# PAGE2_-_SFP_CONNECTORS_POWER.net
KiCad netlist of a schematic drawn in Altium Designer
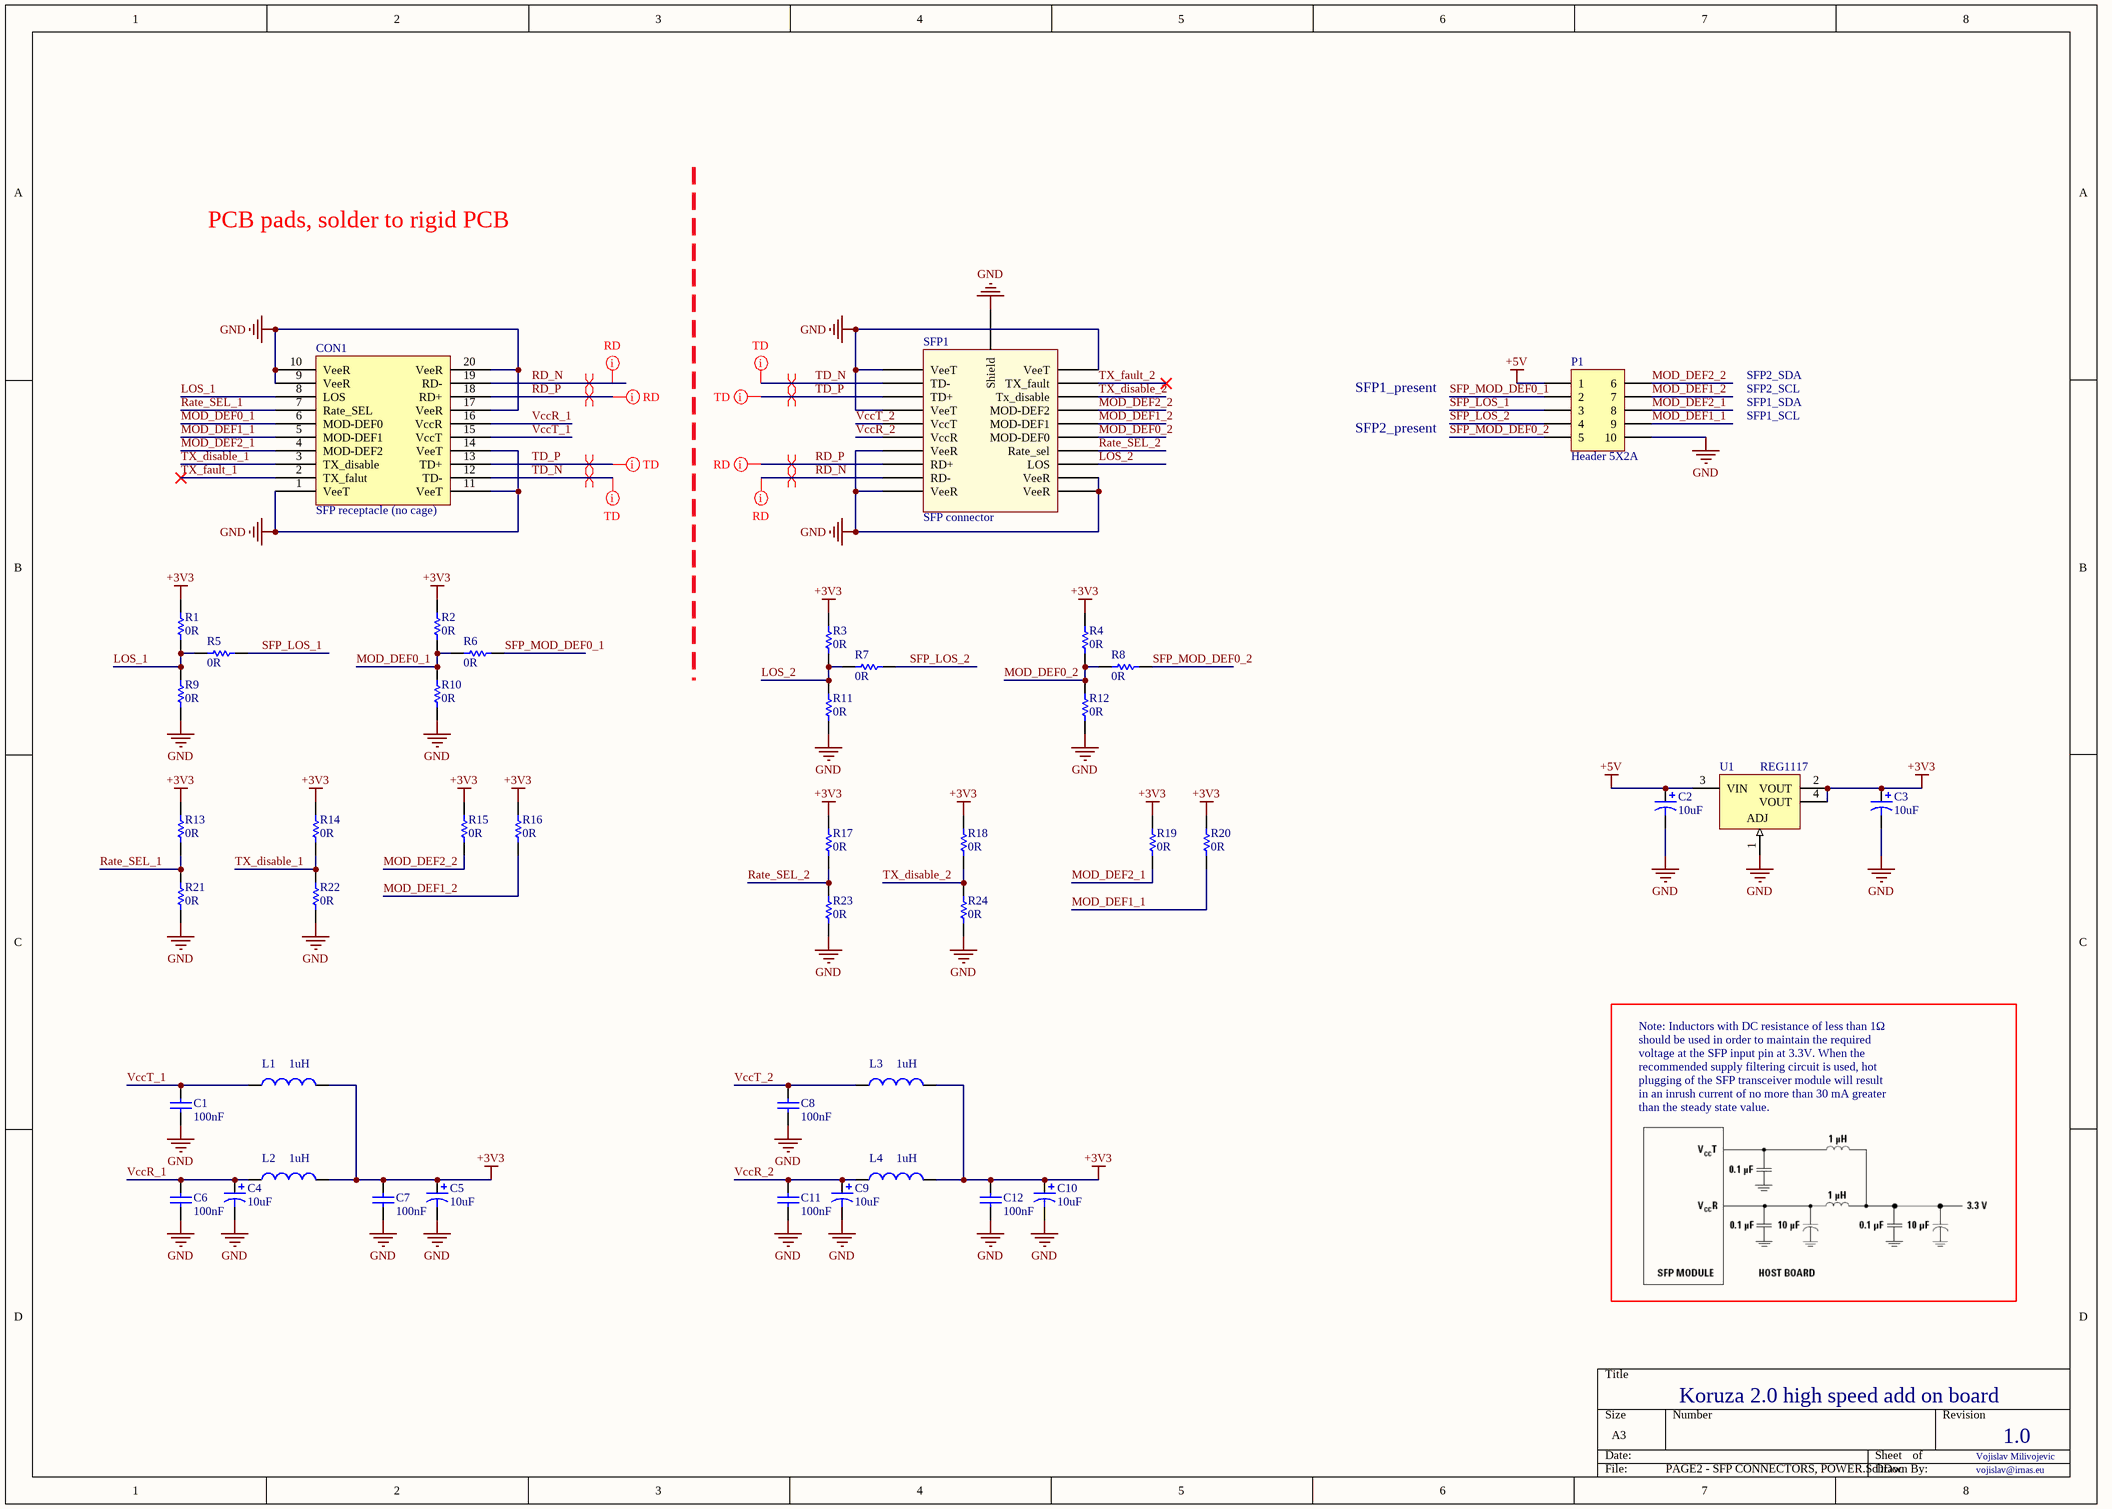
[diagram p0: PAGE2 - SFP CONNECTORS, POWER.SchDoc]

(export (version "E")
  (design (tool "Eeschema 10.0.6"))
  (components
    (comp (ref "C1")
      (value "100nF")
      (footprint "CAP0603")
      (description "Capacitor")
      (fields (field (name "PUBLISHER") "Altium Limited"))
      (libsource (lib "Miscellaneous Devices") (part "Cap"))
    )
    (comp (ref "C2")
      (value "10uF")
      (footprint "CAP0805")
      (description "Polarized Capacitor (Radial)")
      (fields (field (name "PUBLISHER") "Altium Limited"))
      (libsource (lib "PcvLib") (part "CAP0805"))
    )
    (comp (ref "C3")
      (value "10uF")
      (footprint "CAP0805")
      (description "Polarized Capacitor (Radial)")
      (fields (field (name "PUBLISHER") "Altium Limited"))
      (libsource (lib "PcvLib") (part "CAP0805"))
    )
    (comp (ref "C4")
      (value "10uF")
      (footprint "CAP0805")
      (description "Polarized Capacitor (Radial)")
      (fields (field (name "PUBLISHER") "Altium Limited"))
      (libsource (lib "PcvLib") (part "0805_CAP"))
    )
    (comp (ref "C5")
      (value "10uF")
      (footprint "CAP0805")
      (description "Polarized Capacitor (Radial)")
      (fields (field (name "PUBLISHER") "Altium Limited"))
      (libsource (lib "PcvLib") (part "CAP0805"))
    )
    (comp (ref "C6")
      (value "100nF")
      (footprint "CAP0603")
      (description "Capacitor")
      (fields (field (name "PUBLISHER") "Altium Limited"))
      (libsource (lib "altium-import") (part "root_1_Cap_"))
    )
    (comp (ref "C7")
      (value "100nF")
      (footprint "CAP0603")
      (description "Capacitor")
      (fields (field (name "PUBLISHER") "Altium Limited"))
      (libsource (lib "altium-import") (part "root_1_Cap_"))
    )
    (comp (ref "C8")
      (value "100nF")
      (footprint "CAP0603")
      (description "Capacitor")
      (fields (field (name "PUBLISHER") "Altium Limited"))
      (libsource (lib "Miscellaneous Devices") (part "Cap"))
    )
    (comp (ref "C9")
      (value "10uF")
      (footprint "CAP0805")
      (description "Polarized Capacitor (Radial)")
      (fields (field (name "PUBLISHER") "Altium Limited"))
      (libsource (lib "PcvLib") (part "CAP0805"))
    )
    (comp (ref "C10")
      (value "10uF")
      (footprint "CAP0805")
      (description "Polarized Capacitor (Radial)")
      (fields (field (name "PUBLISHER") "Altium Limited"))
      (libsource (lib "PcvLib") (part "CAP0805"))
    )
    (comp (ref "C11")
      (value "100nF")
      (footprint "CAP0603")
      (description "Capacitor")
      (fields (field (name "PUBLISHER") "Altium Limited"))
      (libsource (lib "altium-import") (part "root_1_Cap_"))
    )
    (comp (ref "C12")
      (value "100nF")
      (footprint "CAP0603")
      (description "Capacitor")
      (fields (field (name "PUBLISHER") "Altium Limited"))
      (libsource (lib "altium-import") (part "root_1_Cap_"))
    )
    (comp (ref "CON1")
      (value "SFP receptacle (no cage)")
      (footprint "PCB_SFP")
      (description "SFP receptacle, woutout cage, standard orientation of SFP module")
      (libsource (lib "Connectors") (part "SFP connector"))
    )
    (comp (ref "L1")
      (value "1uH")
      (footprint "6-0805_N")
      (description "Inductor")
      (fields (field (name "PUBLISHER") "Altium Limited"))
      (libsource (lib "Miscellaneous Devices") (part "Inductor"))
    )
    (comp (ref "L2")
      (value "1uH")
      (footprint "6-0805_N")
      (description "Inductor")
      (fields (field (name "PUBLISHER") "Altium Limited"))
      (libsource (lib "Miscellaneous Devices") (part "Inductor"))
    )
    (comp (ref "L3")
      (value "1uH")
      (footprint "6-0805_N")
      (description "Inductor")
      (fields (field (name "PUBLISHER") "Altium Limited"))
      (libsource (lib "Miscellaneous Devices") (part "Inductor"))
    )
    (comp (ref "L4")
      (value "1uH")
      (footprint "6-0805_N")
      (description "Inductor")
      (fields (field (name "PUBLISHER") "Altium Limited"))
      (libsource (lib "Miscellaneous Devices") (part "Inductor"))
    )
    (comp (ref "P1")
      (value "Header 5X2A")
      (footprint "HDR2X5_CEN")
      (description "Header, 5-Pin, Dual row")
      (fields (field (name "PUBLISHER") "Altium Limited"))
      (libsource (lib "Miscellaneous Connectors") (part "Header 5X2A"))
    )
    (comp (ref "R1")
      (value "0R")
      (footprint "RES0603")
      (description "Resistor")
      (fields (field (name "PUBLISHER") "Altium Limited"))
      (libsource (lib "Miscellaneous Devices") (part "Res1"))
    )
    (comp (ref "R2")
      (value "0R")
      (footprint "RES0603")
      (description "Resistor")
      (fields (field (name "PUBLISHER") "Altium Limited"))
      (libsource (lib "Miscellaneous Devices") (part "Res1"))
    )
    (comp (ref "R3")
      (value "0R")
      (footprint "RES0603")
      (description "Resistor")
      (fields (field (name "PUBLISHER") "Altium Limited"))
      (libsource (lib "Miscellaneous Devices") (part "Res1"))
    )
    (comp (ref "R4")
      (value "0R")
      (footprint "RES0603")
      (description "Resistor")
      (fields (field (name "PUBLISHER") "Altium Limited"))
      (libsource (lib "Miscellaneous Devices") (part "Res1"))
    )
    (comp (ref "R5")
      (value "0R")
      (footprint "RES0603")
      (description "Resistor")
      (fields (field (name "PUBLISHER") "Altium Limited"))
      (libsource (lib "Miscellaneous Devices") (part "Res1"))
    )
    (comp (ref "R6")
      (value "0R")
      (footprint "RES0603")
      (description "Resistor")
      (fields (field (name "PUBLISHER") "Altium Limited"))
      (libsource (lib "Miscellaneous Devices") (part "Res1"))
    )
    (comp (ref "R7")
      (value "0R")
      (footprint "RES0603")
      (description "Resistor")
      (fields (field (name "PUBLISHER") "Altium Limited"))
      (libsource (lib "Miscellaneous Devices") (part "Res1"))
    )
    (comp (ref "R8")
      (value "0R")
      (footprint "RES0603")
      (description "Resistor")
      (fields (field (name "PUBLISHER") "Altium Limited"))
      (libsource (lib "Miscellaneous Devices") (part "Res1"))
    )
    (comp (ref "R9")
      (value "0R")
      (footprint "RES0603")
      (description "Resistor")
      (fields (field (name "PUBLISHER") "Altium Limited"))
      (libsource (lib "Miscellaneous Devices") (part "Res1"))
    )
    (comp (ref "R10")
      (value "0R")
      (footprint "RES0603")
      (description "Resistor")
      (fields (field (name "PUBLISHER") "Altium Limited"))
      (libsource (lib "Miscellaneous Devices") (part "Res1"))
    )
    (comp (ref "R11")
      (value "0R")
      (footprint "RES0603")
      (description "Resistor")
      (fields (field (name "PUBLISHER") "Altium Limited"))
      (libsource (lib "Miscellaneous Devices") (part "Res1"))
    )
    (comp (ref "R12")
      (value "0R")
      (footprint "RES0603")
      (description "Resistor")
      (fields (field (name "PUBLISHER") "Altium Limited"))
      (libsource (lib "Miscellaneous Devices") (part "Res1"))
    )
    (comp (ref "R13")
      (value "0R")
      (footprint "RES0603")
      (description "Resistor")
      (fields (field (name "PUBLISHER") "Altium Limited"))
      (libsource (lib "Miscellaneous Devices") (part "Res1"))
    )
    (comp (ref "R14")
      (value "0R")
      (footprint "RES0603")
      (description "Resistor")
      (fields (field (name "PUBLISHER") "Altium Limited"))
      (libsource (lib "Miscellaneous Devices") (part "Res1"))
    )
    (comp (ref "R15")
      (value "0R")
      (footprint "RES0603")
      (description "Resistor")
      (fields (field (name "PUBLISHER") "Altium Limited"))
      (libsource (lib "Miscellaneous Devices") (part "Res1"))
    )
    (comp (ref "R16")
      (value "0R")
      (footprint "RES0603")
      (description "Resistor")
      (fields (field (name "PUBLISHER") "Altium Limited"))
      (libsource (lib "Miscellaneous Devices") (part "Res1"))
    )
    (comp (ref "R17")
      (value "0R")
      (footprint "RES0603")
      (description "Resistor")
      (fields (field (name "PUBLISHER") "Altium Limited"))
      (libsource (lib "Miscellaneous Devices") (part "Res1"))
    )
    (comp (ref "R18")
      (value "0R")
      (footprint "RES0603")
      (description "Resistor")
      (fields (field (name "PUBLISHER") "Altium Limited"))
      (libsource (lib "Miscellaneous Devices") (part "Res1"))
    )
    (comp (ref "R19")
      (value "0R")
      (footprint "RES0603")
      (description "Resistor")
      (fields (field (name "PUBLISHER") "Altium Limited"))
      (libsource (lib "Miscellaneous Devices") (part "Res1"))
    )
    (comp (ref "R20")
      (value "0R")
      (footprint "RES0603")
      (description "Resistor")
      (fields (field (name "PUBLISHER") "Altium Limited"))
      (libsource (lib "Miscellaneous Devices") (part "Res1"))
    )
    (comp (ref "R21")
      (value "0R")
      (footprint "RES0603")
      (description "Resistor")
      (fields (field (name "PUBLISHER") "Altium Limited"))
      (libsource (lib "Miscellaneous Devices") (part "Res1"))
    )
    (comp (ref "R22")
      (value "0R")
      (footprint "RES0603")
      (description "Resistor")
      (fields (field (name "PUBLISHER") "Altium Limited"))
      (libsource (lib "Miscellaneous Devices") (part "Res1"))
    )
    (comp (ref "R23")
      (value "0R")
      (footprint "RES0603")
      (description "Resistor")
      (fields (field (name "PUBLISHER") "Altium Limited"))
      (libsource (lib "Miscellaneous Devices") (part "Res1"))
    )
    (comp (ref "R24")
      (value "0R")
      (footprint "RES0603")
      (description "Resistor")
      (fields (field (name "PUBLISHER") "Altium Limited"))
      (libsource (lib "Miscellaneous Devices") (part "Res1"))
    )
    (comp (ref "SFP1")
      (value "SFP connector")
      (footprint "PCB_SFP_COVER")
      (libsource (lib "GeneralComponents") (part "SFP connector"))
    )
    (comp (ref "U1")
      (value "REG1117")
      (footprint "TI-DCY4_N")
      (fields (field (name "MANUFACTURER") "Texas Instruments"))
      (libsource (lib "TI Power Management Linear Regulator Single Channel LDO (400-7500mA)") (part "REG1117"))
    )
  )
  (nets
    (net (code "1") (name "+3V3") (class "Default")
      (node (ref "C10") (pin "1") (pinfunction "1_1") (pintype "passive"))
      (node (ref "C12") (pin "2") (pinfunction "2_2") (pintype "passive"))
      (node (ref "C3") (pin "1") (pinfunction "1_1") (pintype "passive"))
      (node (ref "C5") (pin "1") (pinfunction "1_1") (pintype "passive"))
      (node (ref "C7") (pin "2") (pinfunction "2_2") (pintype "passive"))
      (node (ref "L1") (pin "2") (pinfunction "2_2") (pintype "passive"))
      (node (ref "L2") (pin "2") (pinfunction "2_2") (pintype "passive"))
      (node (ref "L3") (pin "2") (pinfunction "2_2") (pintype "passive"))
      (node (ref "L4") (pin "2") (pinfunction "2_2") (pintype "passive"))
      (node (ref "R1") (pin "1") (pinfunction "1_1") (pintype "passive"))
      (node (ref "R13") (pin "1") (pinfunction "1_1") (pintype "passive"))
      (node (ref "R14") (pin "1") (pinfunction "1_1") (pintype "passive"))
      (node (ref "R15") (pin "1") (pinfunction "1_1") (pintype "passive"))
      (node (ref "R16") (pin "1") (pinfunction "1_1") (pintype "passive"))
      (node (ref "R17") (pin "1") (pinfunction "1_1") (pintype "passive"))
      (node (ref "R18") (pin "1") (pinfunction "1_1") (pintype "passive"))
      (node (ref "R19") (pin "1") (pinfunction "1_1") (pintype "passive"))
      (node (ref "R2") (pin "1") (pinfunction "1_1") (pintype "passive"))
      (node (ref "R20") (pin "1") (pinfunction "1_1") (pintype "passive"))
      (node (ref "R3") (pin "1") (pinfunction "1_1") (pintype "passive"))
      (node (ref "R4") (pin "1") (pinfunction "1_1") (pintype "passive"))
      (node (ref "U1") (pin "2") (pinfunction "VOUT_2") (pintype "power_in"))
      (node (ref "U1") (pin "4") (pinfunction "VOUT_4") (pintype "power_in"))
    )
    (net (code "2") (name "+5V") (class "Default")
      (node (ref "C2") (pin "1") (pinfunction "1_1") (pintype "passive"))
      (node (ref "P1") (pin "1") (pinfunction "1_1") (pintype "passive"))
      (node (ref "U1") (pin "3") (pinfunction "VIN_3") (pintype "power_in"))
    )
    (net (code "3") (name "/LOS_1") (class "Default")
      (node (ref "CON1") (pin "8") (pinfunction "LOS_8") (pintype "passive"))
      (node (ref "R1") (pin "2") (pinfunction "2_2") (pintype "passive"))
      (node (ref "R5") (pin "1") (pinfunction "1_1") (pintype "passive"))
      (node (ref "R9") (pin "1") (pinfunction "1_1") (pintype "passive"))
    )
    (net (code "4") (name "/LOS_2") (class "Default")
      (node (ref "R11") (pin "1") (pinfunction "1_1") (pintype "passive"))
      (node (ref "R3") (pin "2") (pinfunction "2_2") (pintype "passive"))
      (node (ref "R7") (pin "1") (pinfunction "1_1") (pintype "passive"))
      (node (ref "SFP1") (pin "8") (pinfunction "LOS_8") (pintype "power_in"))
    )
    (net (code "5") (name "/MOD_DEF0_1") (class "Default")
      (node (ref "CON1") (pin "6") (pinfunction "MOD-DEF0_6") (pintype "passive"))
      (node (ref "R10") (pin "1") (pinfunction "1_1") (pintype "passive"))
      (node (ref "R2") (pin "2") (pinfunction "2_2") (pintype "passive"))
      (node (ref "R6") (pin "1") (pinfunction "1_1") (pintype "passive"))
    )
    (net (code "6") (name "/MOD_DEF0_2") (class "Default")
      (node (ref "R12") (pin "1") (pinfunction "1_1") (pintype "passive"))
      (node (ref "R4") (pin "2") (pinfunction "2_2") (pintype "passive"))
      (node (ref "R8") (pin "1") (pinfunction "1_1") (pintype "passive"))
      (node (ref "SFP1") (pin "6") (pinfunction "MOD-DEF0_6") (pintype "power_in"))
    )
    (net (code "7") (name "/MOD_DEF1_1") (class "Default")
      (node (ref "CON1") (pin "5") (pinfunction "MOD-DEF1_5") (pintype "passive"))
      (node (ref "P1") (pin "9") (pinfunction "9_9") (pintype "passive"))
      (node (ref "R20") (pin "2") (pinfunction "2_2") (pintype "passive"))
    )
    (net (code "8") (name "/MOD_DEF1_2") (class "Default")
      (node (ref "P1") (pin "7") (pinfunction "7_7") (pintype "passive"))
      (node (ref "R16") (pin "2") (pinfunction "2_2") (pintype "passive"))
      (node (ref "SFP1") (pin "5") (pinfunction "MOD-DEF1_5") (pintype "power_in"))
    )
    (net (code "9") (name "/MOD_DEF2_1") (class "Default")
      (node (ref "CON1") (pin "4") (pinfunction "MOD-DEF2_4") (pintype "passive"))
      (node (ref "P1") (pin "8") (pinfunction "8_8") (pintype "passive"))
      (node (ref "R19") (pin "2") (pinfunction "2_2") (pintype "passive"))
    )
    (net (code "10") (name "/MOD_DEF2_2") (class "Default")
      (node (ref "P1") (pin "6") (pinfunction "6_6") (pintype "passive"))
      (node (ref "R15") (pin "2") (pinfunction "2_2") (pintype "passive"))
      (node (ref "SFP1") (pin "4") (pinfunction "MOD-DEF2_4") (pintype "power_in"))
    )
    (net (code "11") (name "/RD_N") (class "Default")
      (node (ref "CON1") (pin "19") (pinfunction "RD-_19") (pintype "passive"))
      (node (ref "SFP1") (pin "12") (pinfunction "RD-_12") (pintype "power_in"))
    )
    (net (code "12") (name "/RD_P") (class "Default")
      (node (ref "CON1") (pin "18") (pinfunction "RD+_18") (pintype "passive"))
      (node (ref "SFP1") (pin "13") (pinfunction "RD+_13") (pintype "power_in"))
    )
    (net (code "13") (name "/Rate_SEL_1") (class "Default")
      (node (ref "CON1") (pin "7") (pinfunction "Rate_SEL_7") (pintype "passive"))
      (node (ref "R13") (pin "2") (pinfunction "2_2") (pintype "passive"))
      (node (ref "R21") (pin "1") (pinfunction "1_1") (pintype "passive"))
    )
    (net (code "14") (name "/Rate_SEL_2") (class "Default")
      (node (ref "R17") (pin "2") (pinfunction "2_2") (pintype "passive"))
      (node (ref "R23") (pin "1") (pinfunction "1_1") (pintype "passive"))
      (node (ref "SFP1") (pin "7") (pinfunction "Rate_sel_7") (pintype "power_in"))
    )
    (net (code "15") (name "/SFP_LOS_1") (class "Default")
      (node (ref "P1") (pin "3") (pinfunction "3_3") (pintype "passive"))
      (node (ref "R5") (pin "2") (pinfunction "2_2") (pintype "passive"))
    )
    (net (code "16") (name "/SFP_LOS_2") (class "Default")
      (node (ref "P1") (pin "4") (pinfunction "4_4") (pintype "passive"))
      (node (ref "R7") (pin "2") (pinfunction "2_2") (pintype "passive"))
    )
    (net (code "17") (name "/SFP_MOD_DEF0_1") (class "Default")
      (node (ref "P1") (pin "2") (pinfunction "2_2") (pintype "passive"))
      (node (ref "R6") (pin "2") (pinfunction "2_2") (pintype "passive"))
    )
    (net (code "18") (name "/SFP_MOD_DEF0_2") (class "Default")
      (node (ref "P1") (pin "5") (pinfunction "5_5") (pintype "passive"))
      (node (ref "R8") (pin "2") (pinfunction "2_2") (pintype "passive"))
    )
    (net (code "19") (name "/TD_N") (class "Default")
      (node (ref "CON1") (pin "12") (pinfunction "TD-_12") (pintype "passive"))
      (node (ref "SFP1") (pin "19") (pinfunction "TD-_19") (pintype "power_in"))
    )
    (net (code "20") (name "/TD_P") (class "Default")
      (node (ref "CON1") (pin "13") (pinfunction "TD+_13") (pintype "passive"))
      (node (ref "SFP1") (pin "18") (pinfunction "TD+_18") (pintype "power_in"))
    )
    (net (code "21") (name "/TX_disable_1") (class "Default")
      (node (ref "CON1") (pin "3") (pinfunction "TX_disable_3") (pintype "passive"))
      (node (ref "R14") (pin "2") (pinfunction "2_2") (pintype "passive"))
      (node (ref "R22") (pin "1") (pinfunction "1_1") (pintype "passive"))
    )
    (net (code "22") (name "/TX_disable_2") (class "Default")
      (node (ref "R18") (pin "2") (pinfunction "2_2") (pintype "passive"))
      (node (ref "R24") (pin "1") (pinfunction "1_1") (pintype "passive"))
      (node (ref "SFP1") (pin "3") (pinfunction "Tx_disable_3") (pintype "power_in"))
    )
    (net (code "23") (name "/TX_fault_1") (class "Default")
      (node (ref "CON1") (pin "2") (pinfunction "TX_falut_2") (pintype "passive+no_connect"))
    )
    (net (code "24") (name "/TX_fault_2") (class "Default")
      (node (ref "SFP1") (pin "2") (pinfunction "TX_fault_2") (pintype "power_in+no_connect"))
    )
    (net (code "25") (name "/VccR_1") (class "Default")
      (node (ref "C4") (pin "1") (pinfunction "1_1") (pintype "passive"))
      (node (ref "C6") (pin "2") (pinfunction "2_2") (pintype "passive"))
      (node (ref "CON1") (pin "16") (pinfunction "VccR_16") (pintype "passive"))
      (node (ref "L2") (pin "1") (pinfunction "1_1") (pintype "passive"))
    )
    (net (code "26") (name "/VccR_2") (class "Default")
      (node (ref "C11") (pin "2") (pinfunction "2_2") (pintype "passive"))
      (node (ref "C9") (pin "1") (pinfunction "1_1") (pintype "passive"))
      (node (ref "L4") (pin "1") (pinfunction "1_1") (pintype "passive"))
      (node (ref "SFP1") (pin "15") (pinfunction "VccR_15") (pintype "power_in"))
    )
    (net (code "27") (name "/VccT_1") (class "Default")
      (node (ref "C1") (pin "2") (pinfunction "2_2") (pintype "passive"))
      (node (ref "CON1") (pin "15") (pinfunction "VccT_15") (pintype "passive"))
      (node (ref "L1") (pin "1") (pinfunction "1_1") (pintype "passive"))
    )
    (net (code "28") (name "/VccT_2") (class "Default")
      (node (ref "C8") (pin "2") (pinfunction "2_2") (pintype "passive"))
      (node (ref "L3") (pin "1") (pinfunction "1_1") (pintype "passive"))
      (node (ref "SFP1") (pin "16") (pinfunction "VccT_16") (pintype "power_in"))
    )
    (net (code "29") (name "GND") (class "Default")
      (node (ref "C1") (pin "1") (pinfunction "1_1") (pintype "passive"))
      (node (ref "C10") (pin "2") (pinfunction "2_2") (pintype "passive"))
      (node (ref "C11") (pin "1") (pinfunction "1_1") (pintype "passive"))
      (node (ref "C12") (pin "1") (pinfunction "1_1") (pintype "passive"))
      (node (ref "C2") (pin "2") (pinfunction "2_2") (pintype "passive"))
      (node (ref "C3") (pin "2") (pinfunction "2_2") (pintype "passive"))
      (node (ref "C4") (pin "2") (pinfunction "2_2") (pintype "passive"))
      (node (ref "C5") (pin "2") (pinfunction "2_2") (pintype "passive"))
      (node (ref "C6") (pin "1") (pinfunction "1_1") (pintype "passive"))
      (node (ref "C7") (pin "1") (pinfunction "1_1") (pintype "passive"))
      (node (ref "C8") (pin "1") (pinfunction "1_1") (pintype "passive"))
      (node (ref "C9") (pin "2") (pinfunction "2_2") (pintype "passive"))
      (node (ref "CON1") (pin "1") (pinfunction "VeeT_1") (pintype "passive"))
      (node (ref "CON1") (pin "10") (pinfunction "VeeR_10") (pintype "passive"))
      (node (ref "CON1") (pin "11") (pinfunction "VeeT_11") (pintype "passive"))
      (node (ref "CON1") (pin "14") (pinfunction "VeeT_14") (pintype "passive"))
      (node (ref "CON1") (pin "17") (pinfunction "VeeR_17") (pintype "passive"))
      (node (ref "CON1") (pin "20") (pinfunction "VeeR_20") (pintype "passive"))
      (node (ref "CON1") (pin "9") (pinfunction "VeeR_9") (pintype "passive"))
      (node (ref "P1") (pin "10") (pinfunction "10_10") (pintype "passive"))
      (node (ref "R10") (pin "2") (pinfunction "2_2") (pintype "passive"))
      (node (ref "R11") (pin "2") (pinfunction "2_2") (pintype "passive"))
      (node (ref "R12") (pin "2") (pinfunction "2_2") (pintype "passive"))
      (node (ref "R21") (pin "2") (pinfunction "2_2") (pintype "passive"))
      (node (ref "R22") (pin "2") (pinfunction "2_2") (pintype "passive"))
      (node (ref "R23") (pin "2") (pinfunction "2_2") (pintype "passive"))
      (node (ref "R24") (pin "2") (pinfunction "2_2") (pintype "passive"))
      (node (ref "R9") (pin "2") (pinfunction "2_2") (pintype "passive"))
      (node (ref "SFP1") (pin "1") (pinfunction "VeeT_1") (pintype "power_in"))
      (node (ref "SFP1") (pin "10") (pinfunction "VeeR_10") (pintype "power_in"))
      (node (ref "SFP1") (pin "11") (pinfunction "VeeR_11") (pintype "power_in"))
      (node (ref "SFP1") (pin "14") (pinfunction "VeeR_14") (pintype "power_in"))
      (node (ref "SFP1") (pin "17") (pinfunction "VeeT_17") (pintype "power_in"))
      (node (ref "SFP1") (pin "20") (pinfunction "VeeT_20") (pintype "power_in"))
      (node (ref "SFP1") (pin "21") (pinfunction "Shield_21") (pintype "power_in"))
      (node (ref "SFP1") (pin "9") (pinfunction "VeeR_9") (pintype "power_in"))
      (node (ref "U1") (pin "1") (pinfunction "ADJ_1") (pintype "input"))
    )
  )
)
